# working.net
KiCad netlist of a schematic drawn in EAGLE
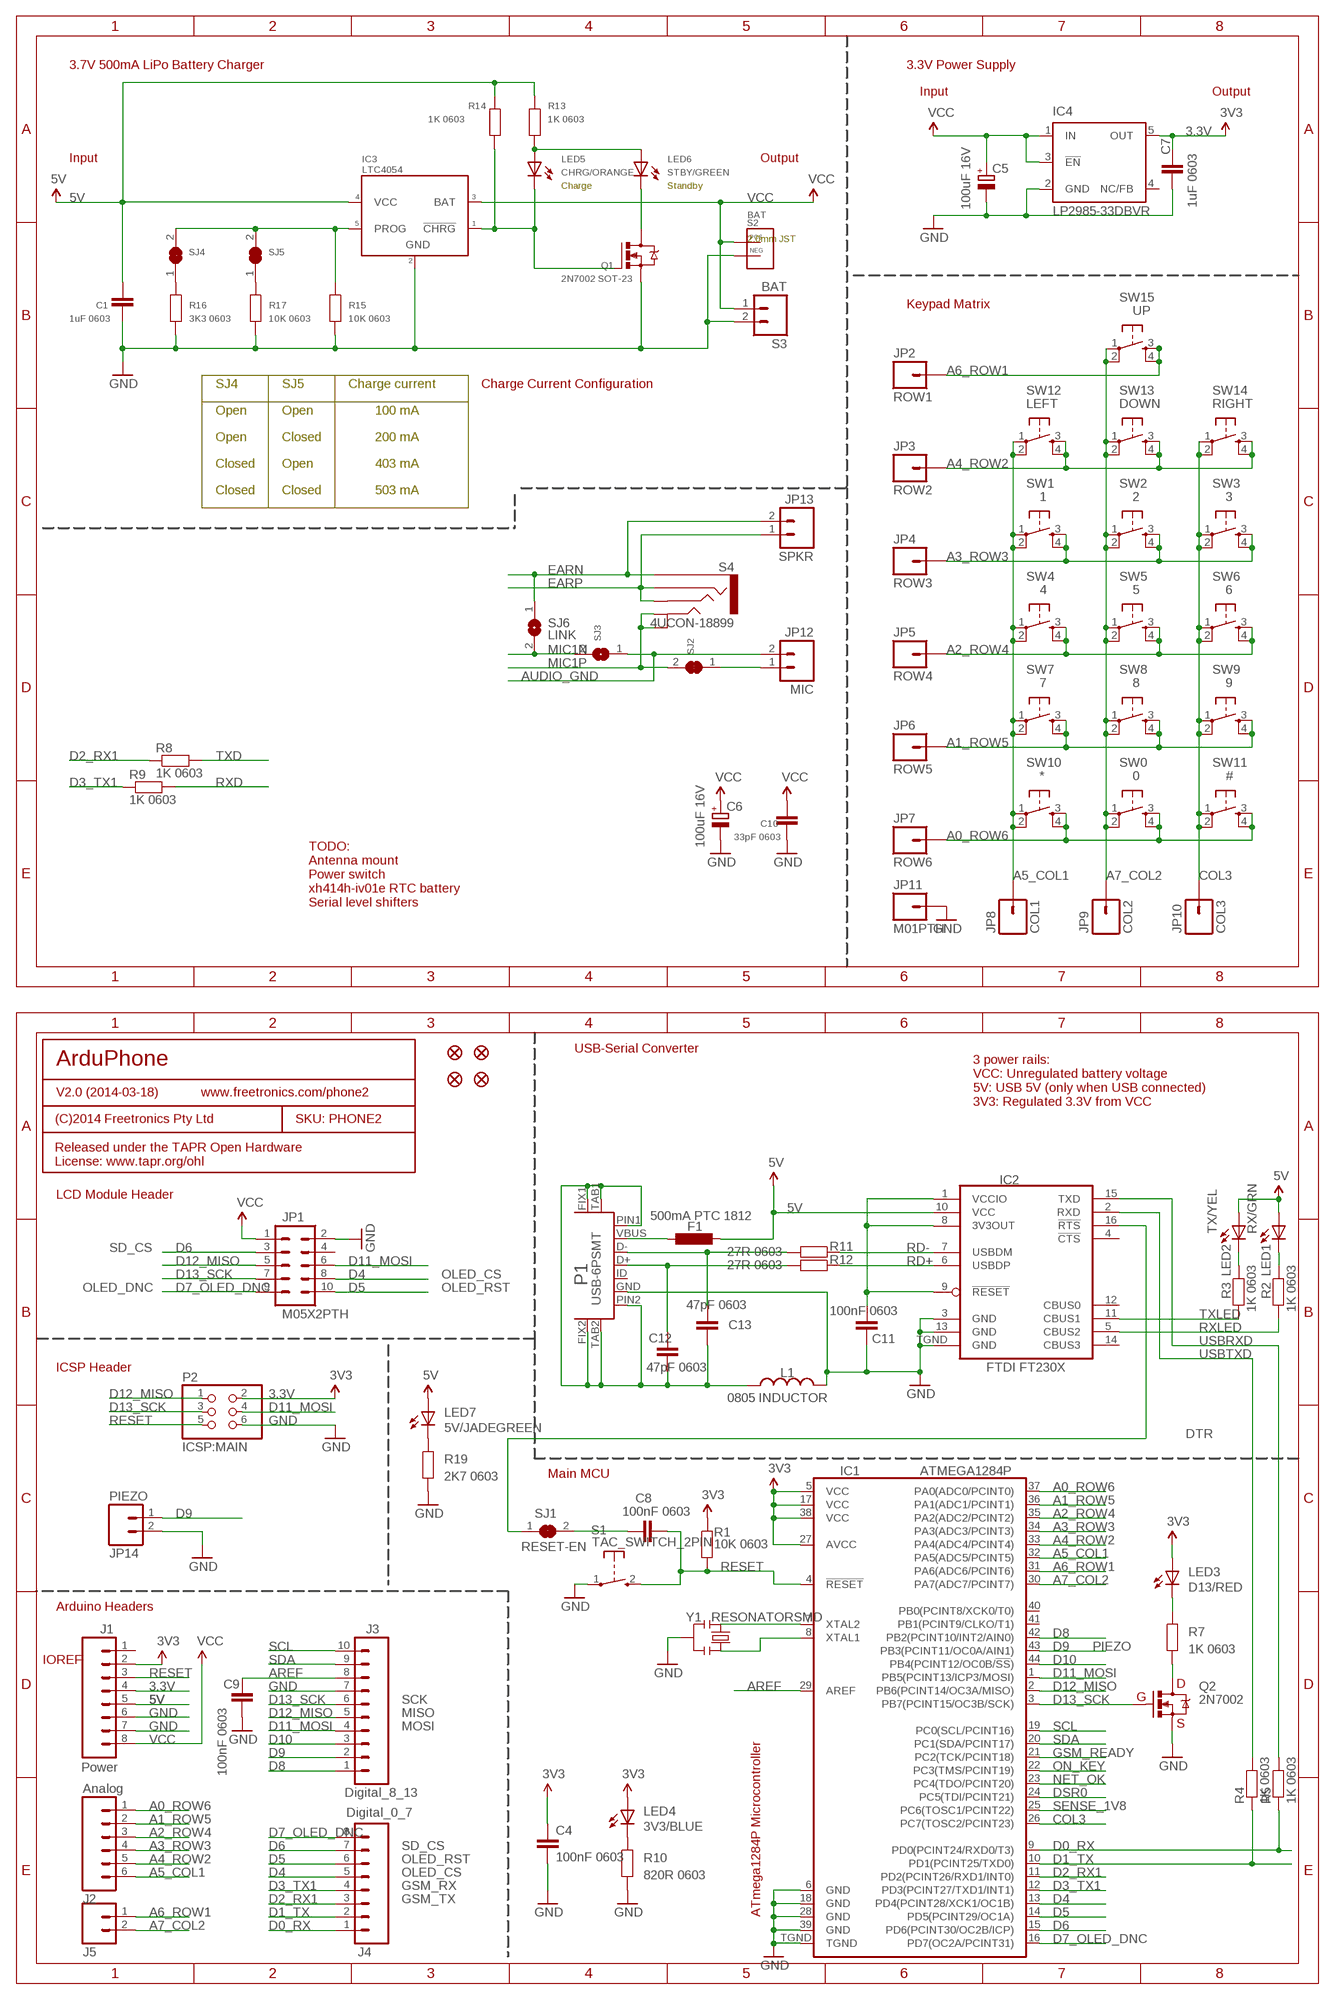
[diagram p0: schematic, sheet 1, part 1 of 2]
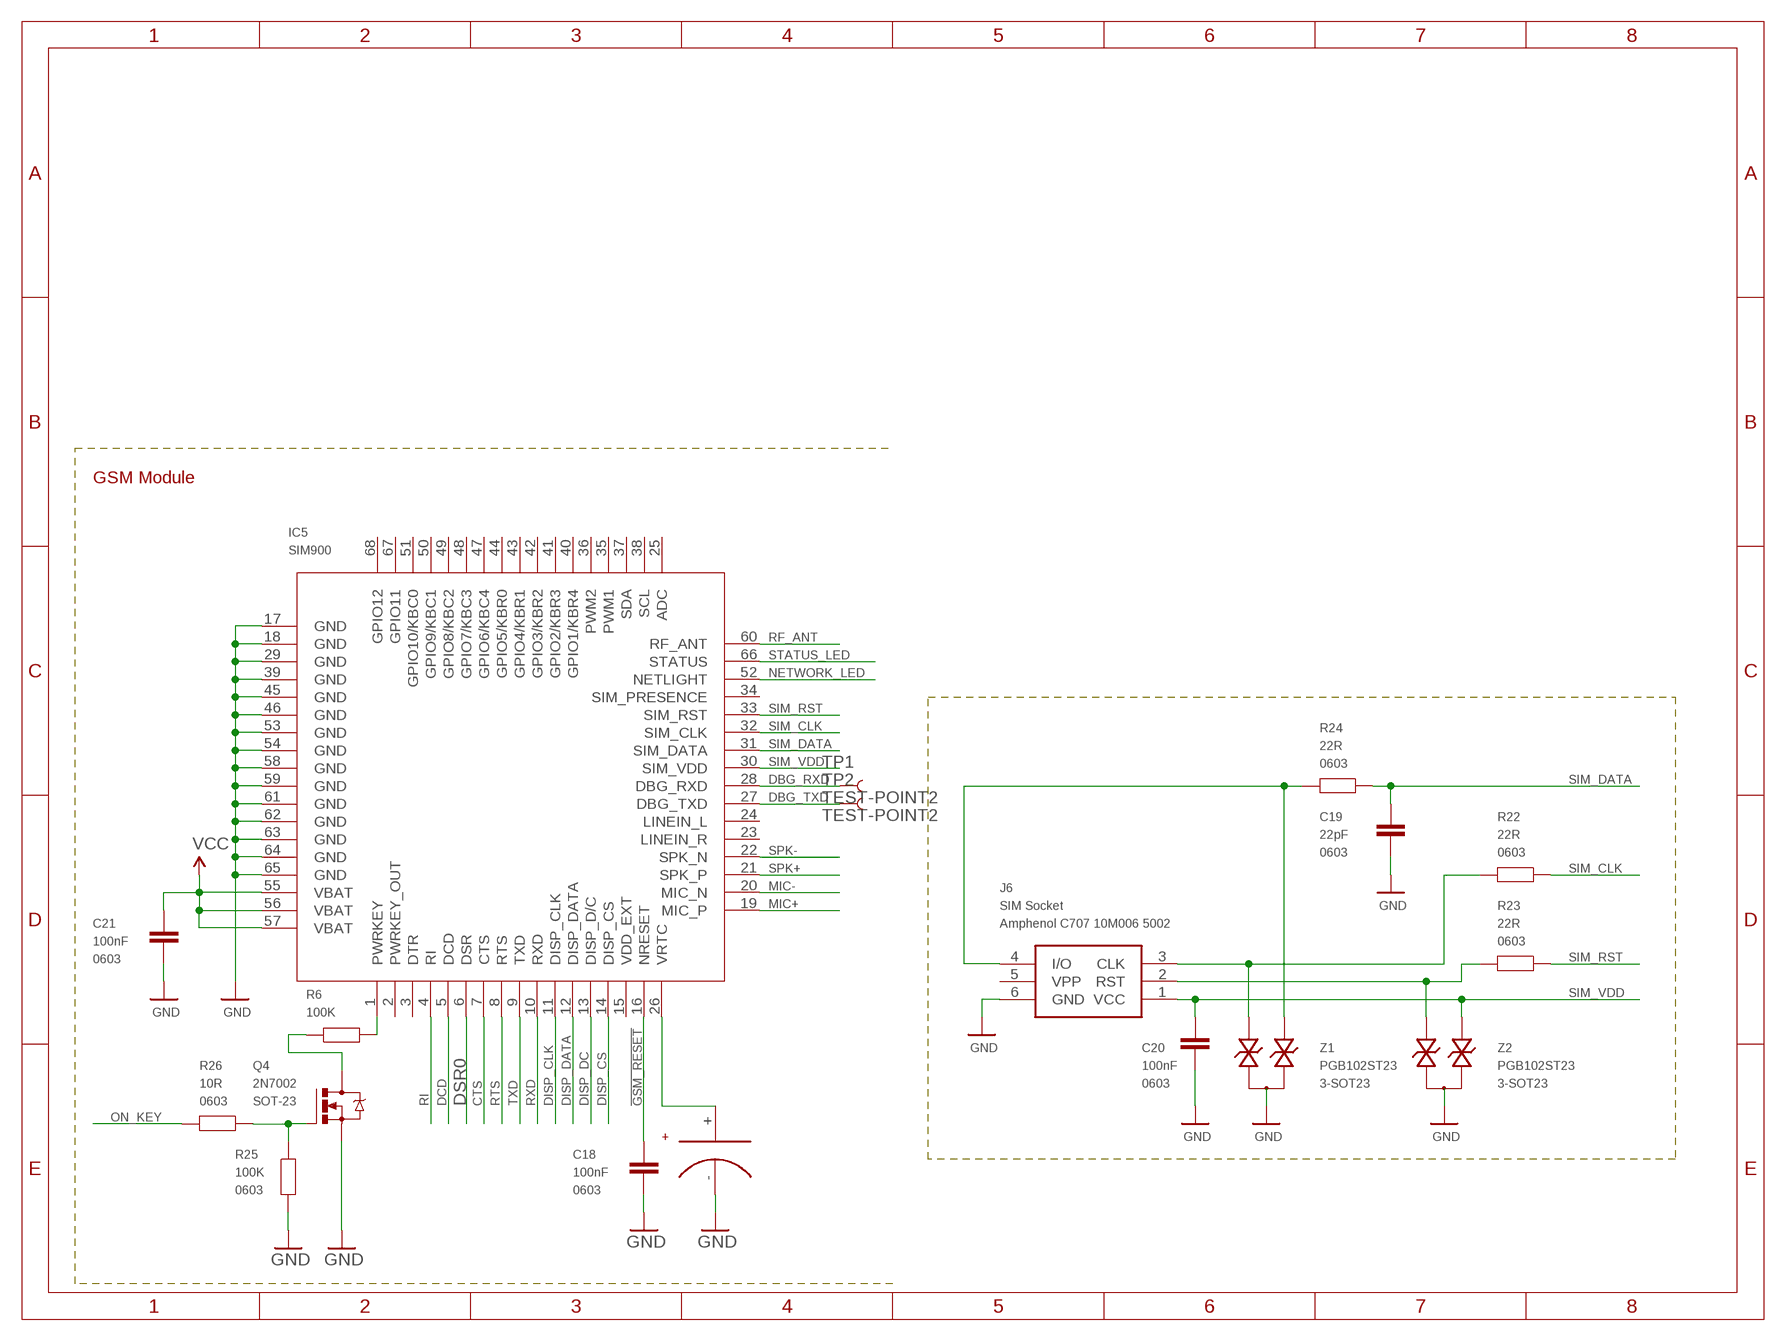
[diagram p1: schematic, sheet 1, part 2 of 2]

(export (version "E")
  (design (tool "Eeschema 10.0.6"))
  (components
    (comp (ref "C1")
      (value "1uF 0603")
      (footprint "eagle-import:0603")
      (libsource (lib "eagle-import") (part "freetronics-master-v1.1_CAP0603"))
    )
    (comp (ref "C4")
      (value "100nF 0603")
      (footprint "eagle-import:0603")
      (libsource (lib "eagle-import") (part "freetronics-master-v1.1_CAP0603"))
    )
    (comp (ref "C5")
      (value "100uF 16V")
      (footprint "eagle-import:PANASONIC_D")
      (libsource (lib "eagle-import") (part "CPOL-EUD"))
    )
    (comp (ref "C6")
      (value "100uF 16V")
      (footprint "eagle-import:PANASONIC_D")
      (libsource (lib "eagle-import") (part "CPOL-EUD"))
    )
    (comp (ref "C7")
      (value "1uF 0603")
      (footprint "eagle-import:0603")
      (libsource (lib "eagle-import") (part "freetronics-master-v1.1_CAP0603"))
    )
    (comp (ref "C8")
      (value "100nF 0603")
      (footprint "eagle-import:0603")
      (libsource (lib "eagle-import") (part "freetronics-master-v1.1_CAP0603"))
    )
    (comp (ref "C9")
      (value "100nF 0603")
      (footprint "eagle-import:0603")
      (libsource (lib "eagle-import") (part "freetronics-master-v1.1_CAP0603"))
    )
    (comp (ref "C10")
      (value "33pF 0603")
      (footprint "eagle-import:0603@1")
      (libsource (lib "eagle-import") (part "CAP0603"))
    )
    (comp (ref "C11")
      (value "100nF 0603")
      (footprint "eagle-import:0603")
      (libsource (lib "eagle-import") (part "freetronics-master-v1.1_CAP0603"))
    )
    (comp (ref "C12")
      (value "47pF 0603")
      (footprint "eagle-import:C0603")
      (libsource (lib "eagle-import") (part "C-EUC0603"))
    )
    (comp (ref "C13")
      (value "47pF 0603")
      (footprint "eagle-import:C0603")
      (libsource (lib "eagle-import") (part "C-EUC0603"))
    )
    (comp (ref "C18")
      (value "100nF")
      (footprint "eagle-import:0603")
      (fields (field (name "PACKAGE") "0603"))
      (libsource (lib "eagle-import") (part "freetronics-master-v1_CAP0603"))
    )
    (comp (ref "C19")
      (value "22pF")
      (footprint "eagle-import:0603")
      (fields (field (name "PACKAGE") "0603"))
      (libsource (lib "eagle-import") (part "freetronics-master-v1_CAP0603"))
    )
    (comp (ref "C20")
      (value "100nF")
      (footprint "eagle-import:0603")
      (fields (field (name "PACKAGE") "0603"))
      (libsource (lib "eagle-import") (part "freetronics-master-v1_CAP0603"))
    )
    (comp (ref "C21")
      (value "100nF")
      (footprint "eagle-import:0603")
      (fields (field (name "PACKAGE") "0603"))
      (libsource (lib "eagle-import") (part "freetronics-master-v1_CAP0603"))
    )
    (comp (ref "F1")
      (value "500mA PTC 1812")
      (footprint "eagle-import:L1812")
      (libsource (lib "eagle-import") (part "L-EUL1812"))
    )
    (comp (ref "IC1")
      (value "ATMEGA1284P")
      (footprint "eagle-import:QFN-44M1")
      (libsource (lib "eagle-import") (part "ATMEGA1284P"))
    )
    (comp (ref "IC2")
      (value "FT230X")
      (footprint "eagle-import:QFN-16")
      (libsource (lib "eagle-import") (part "FT230X"))
    )
    (comp (ref "IC3")
      (value "LTC4054")
      (footprint "eagle-import:SOT23-5")
      (libsource (lib "eagle-import") (part "LTC4054"))
    )
    (comp (ref "IC4")
      (value "LP2985-33DBVR")
      (footprint "eagle-import:TEXAS_SOT23-DBV")
      (libsource (lib "eagle-import") (part "TEXAS_TPS77033"))
    )
    (comp (ref "IC5")
      (value "SIM900")
      (footprint "eagle-import:SIM900")
      (libsource (lib "eagle-import") (part "SIM900"))
    )
    (comp (ref "J1")
      (value "Power")
      (footprint "eagle-import:1X08")
      (libsource (lib "eagle-import") (part "M08"))
    )
    (comp (ref "J2")
      (value "Analog")
      (footprint "eagle-import:1X06")
      (libsource (lib "eagle-import") (part "M06SIP"))
    )
    (comp (ref "J3")
      (value "Digital_8_13")
      (footprint "eagle-import:1X10")
      (libsource (lib "eagle-import") (part "M100.1"))
    )
    (comp (ref "J4")
      (value "Digital_0_7")
      (footprint "eagle-import:1X08")
      (libsource (lib "eagle-import") (part "M08"))
    )
    (comp (ref "J5")
      (value "M02PTH")
      (footprint "eagle-import:1X02")
      (libsource (lib "eagle-import") (part "M02PTH"))
    )
    (comp (ref "J6")
      (value "SIM Socket")
      (footprint "eagle-import:SIMHOLDER3")
      (fields (field (name "ID") "Amphenol C707 10M006 5002"))
      (libsource (lib "eagle-import") (part "SIMHOLDER3"))
    )
    (comp (ref "JP1")
      (value "M05X2PTH")
      (footprint "eagle-import:AVR_ICSP")
      (libsource (lib "eagle-import") (part "M05X2PTH"))
    )
    (comp (ref "JP2")
      (value "ROW1")
      (footprint "eagle-import:1X01")
      (libsource (lib "eagle-import") (part "M01PTH"))
    )
    (comp (ref "JP3")
      (value "ROW2")
      (footprint "eagle-import:1X01")
      (libsource (lib "eagle-import") (part "M01PTH"))
    )
    (comp (ref "JP4")
      (value "ROW3")
      (footprint "eagle-import:1X01")
      (libsource (lib "eagle-import") (part "M01PTH"))
    )
    (comp (ref "JP5")
      (value "ROW4")
      (footprint "eagle-import:1X01")
      (libsource (lib "eagle-import") (part "M01PTH"))
    )
    (comp (ref "JP6")
      (value "ROW5")
      (footprint "eagle-import:1X01")
      (libsource (lib "eagle-import") (part "M01PTH"))
    )
    (comp (ref "JP7")
      (value "ROW6")
      (footprint "eagle-import:1X01")
      (libsource (lib "eagle-import") (part "M01PTH"))
    )
    (comp (ref "JP8")
      (value "COL1")
      (footprint "eagle-import:1X01")
      (libsource (lib "eagle-import") (part "M01PTH"))
    )
    (comp (ref "JP9")
      (value "COL2")
      (footprint "eagle-import:1X01")
      (libsource (lib "eagle-import") (part "M01PTH"))
    )
    (comp (ref "JP10")
      (value "COL3")
      (footprint "eagle-import:1X01")
      (libsource (lib "eagle-import") (part "M01PTH"))
    )
    (comp (ref "JP11")
      (value "M01PTH")
      (footprint "eagle-import:1X01")
      (libsource (lib "eagle-import") (part "freetronics-original_M01PTH"))
    )
    (comp (ref "JP12")
      (value "MIC")
      (footprint "eagle-import:1X02")
      (libsource (lib "eagle-import") (part "M02PTH"))
    )
    (comp (ref "JP13")
      (value "SPKR")
      (footprint "eagle-import:1X02")
      (libsource (lib "eagle-import") (part "M02PTH"))
    )
    (comp (ref "JP14")
      (value "PIEZO")
      (footprint "eagle-import:1X02")
      (libsource (lib "eagle-import") (part "M02PTH"))
    )
    (comp (ref "L1")
      (value "0805 INDUCTOR")
      (footprint "eagle-import:0805-LARGE")
      (libsource (lib "eagle-import") (part "INDUCTOR0805-LARGE"))
    )
    (comp (ref "LED1")
      (value "RX/GRN")
      (footprint "eagle-import:LED-0603")
      (libsource (lib "eagle-import") (part "LED0603"))
    )
    (comp (ref "LED2")
      (value "TX/YEL")
      (footprint "eagle-import:LED-0603")
      (libsource (lib "eagle-import") (part "LED0603"))
    )
    (comp (ref "LED3")
      (value "D13/RED")
      (footprint "eagle-import:LED-0603")
      (libsource (lib "eagle-import") (part "LED0603"))
    )
    (comp (ref "LED4")
      (value "3V3/BLUE")
      (footprint "eagle-import:LED-0603")
      (libsource (lib "eagle-import") (part "LED0603"))
    )
    (comp (ref "LED5")
      (value "CHRG/ORANGE")
      (footprint "eagle-import:LED-0603")
      (libsource (lib "eagle-import") (part "LED0603"))
    )
    (comp (ref "LED6")
      (value "STBY/GREEN")
      (footprint "eagle-import:LED-0603")
      (libsource (lib "eagle-import") (part "LED0603"))
    )
    (comp (ref "LED7")
      (value "5V/JADEGREEN")
      (footprint "eagle-import:LED-0603")
      (libsource (lib "eagle-import") (part "LED0603"))
    )
    (comp (ref "P1")
      (value "USB-6PSMT")
      (footprint "eagle-import:USB-MICROB-MB05PMXX")
      (libsource (lib "eagle-import") (part "USB-6PSMT"))
    )
    (comp (ref "P2")
      (value "ICSP:MAIN")
      (footprint "eagle-import:2X03")
      (libsource (lib "eagle-import") (part "PINHD-2X3"))
    )
    (comp (ref "Q1")
      (value "2N7002 SOT-23")
      (footprint "eagle-import:SOT23-3")
      (libsource (lib "eagle-import") (part "2N7002"))
    )
    (comp (ref "Q2")
      (value "2N7002")
      (footprint "eagle-import:SOT23-3")
      (libsource (lib "eagle-import") (part "MOSFET-NCHANNELSMD"))
    )
    (comp (ref "Q4")
      (value "2N7002")
      (footprint "eagle-import:SOT23-3")
      (fields (field (name "PACKAGE") "SOT-23"))
      (libsource (lib "eagle-import") (part "2N7002"))
    )
    (comp (ref "R1")
      (value "10K 0603")
      (footprint "eagle-import:0603")
      (libsource (lib "eagle-import") (part "freetronics-master-v1.1_RESISTOR0603"))
    )
    (comp (ref "R2")
      (value "1K 0603")
      (footprint "eagle-import:0603")
      (libsource (lib "eagle-import") (part "freetronics-master-v1.1_RESISTOR0603"))
    )
    (comp (ref "R3")
      (value "1K 0603")
      (footprint "eagle-import:0603")
      (libsource (lib "eagle-import") (part "freetronics-master-v1.1_RESISTOR0603"))
    )
    (comp (ref "R4")
      (value "1K 0603")
      (footprint "eagle-import:0603")
      (libsource (lib "eagle-import") (part "freetronics-master-v1.1_RESISTOR0603"))
    )
    (comp (ref "R5")
      (value "1K 0603")
      (footprint "eagle-import:0603")
      (libsource (lib "eagle-import") (part "freetronics-master-v1.1_RESISTOR0603"))
    )
    (comp (ref "R6")
      (value "100K")
      (footprint "eagle-import:0603")
      (fields (field (name "PACKAGE") "0603"))
      (libsource (lib "eagle-import") (part "RESISTOR0603"))
    )
    (comp (ref "R7")
      (value "1K 0603")
      (footprint "eagle-import:0603")
      (libsource (lib "eagle-import") (part "freetronics-master-v1.1_RESISTOR0603"))
    )
    (comp (ref "R8")
      (value "1K 0603")
      (footprint "eagle-import:0603")
      (libsource (lib "eagle-import") (part "freetronics-master-v1.1_RESISTOR0603"))
    )
    (comp (ref "R9")
      (value "1K 0603")
      (footprint "eagle-import:0603")
      (libsource (lib "eagle-import") (part "freetronics-master-v1.1_RESISTOR0603"))
    )
    (comp (ref "R10")
      (value "820R 0603")
      (footprint "eagle-import:0603")
      (libsource (lib "eagle-import") (part "freetronics-master-v1.1_RESISTOR0603"))
    )
    (comp (ref "R11")
      (value "27R 0603")
      (footprint "eagle-import:0603")
      (libsource (lib "eagle-import") (part "freetronics-master-v1.1_RESISTOR0603"))
    )
    (comp (ref "R12")
      (value "27R 0603")
      (footprint "eagle-import:0603")
      (libsource (lib "eagle-import") (part "freetronics-master-v1.1_RESISTOR0603"))
    )
    (comp (ref "R13")
      (value "1K 0603")
      (footprint "eagle-import:0603")
      (libsource (lib "eagle-import") (part "freetronics-master-v1.1_RESISTOR0603"))
    )
    (comp (ref "R14")
      (value "1K 0603")
      (footprint "eagle-import:0603")
      (libsource (lib "eagle-import") (part "freetronics-master-v1.1_RESISTOR0603"))
    )
    (comp (ref "R15")
      (value "10K 0603")
      (footprint "eagle-import:0603")
      (libsource (lib "eagle-import") (part "freetronics-master-v1.1_RESISTOR0603"))
    )
    (comp (ref "R16")
      (value "3K3 0603")
      (footprint "eagle-import:0603")
      (libsource (lib "eagle-import") (part "freetronics-master-v1.1_RESISTOR0603"))
    )
    (comp (ref "R17")
      (value "10K 0603")
      (footprint "eagle-import:0603")
      (libsource (lib "eagle-import") (part "freetronics-master-v1.1_RESISTOR0603"))
    )
    (comp (ref "R19")
      (value "2K7 0603")
      (footprint "eagle-import:0603")
      (libsource (lib "eagle-import") (part "freetronics-master-v1.1_RESISTOR0603"))
    )
    (comp (ref "R22")
      (value "22R")
      (footprint "eagle-import:0603")
      (fields (field (name "PACKAGE") "0603"))
      (libsource (lib "eagle-import") (part "RESISTOR0603"))
    )
    (comp (ref "R23")
      (value "22R")
      (footprint "eagle-import:0603")
      (fields (field (name "PACKAGE") "0603"))
      (libsource (lib "eagle-import") (part "RESISTOR0603"))
    )
    (comp (ref "R24")
      (value "22R")
      (footprint "eagle-import:0603")
      (fields (field (name "PACKAGE") "0603"))
      (libsource (lib "eagle-import") (part "RESISTOR0603"))
    )
    (comp (ref "R25")
      (value "100K")
      (footprint "eagle-import:0603")
      (fields (field (name "PACKAGE") "0603"))
      (libsource (lib "eagle-import") (part "RESISTOR0603"))
    )
    (comp (ref "R26")
      (value "10R")
      (footprint "eagle-import:0603")
      (fields (field (name "PACKAGE") "0603"))
      (libsource (lib "eagle-import") (part "RESISTOR0603"))
    )
    (comp (ref "S1")
      (value "TAC_SWITCH_2PIN")
      (footprint "eagle-import:TACTILE_SWITCH_SMD_2PIN_TINY")
      (libsource (lib "eagle-import") (part "TAC_SWITCH_2PIN"))
    )
    (comp (ref "S2")
      (value "BAT")
      (footprint "eagle-import:JST-2MM-TH-RA")
      (libsource (lib "eagle-import") (part "2P-JST-TH-RAPTH"))
    )
    (comp (ref "S3")
      (value "BAT")
      (footprint "eagle-import:1X02")
      (libsource (lib "eagle-import") (part "M02PTH"))
    )
    (comp (ref "S4")
      (value "4UCON-18899")
      (footprint "eagle-import:4UCON-18899")
      (libsource (lib "eagle-import") (part "AUDIO-JACK-4POLE"))
    )
    (comp (ref "SJ1")
      (value "RESET-EN")
      (footprint "eagle-import:SJC")
      (libsource (lib "eagle-import") (part "SJCN"))
    )
    (comp (ref "SJ2")
      (value "SJCN")
      (footprint "eagle-import:SJC")
      (libsource (lib "eagle-import") (part "SJCN"))
    )
    (comp (ref "SJ3") (value "SJ") (footprint "eagle-import:SJ") (libsource (lib "eagle-import") (part "SJ")))
    (comp (ref "SJ4")
      (value "SJCN")
      (footprint "eagle-import:SJC")
      (libsource (lib "eagle-import") (part "SJCN"))
    )
    (comp (ref "SJ5")
      (value "SJCN")
      (footprint "eagle-import:SJC")
      (libsource (lib "eagle-import") (part "SJCN"))
    )
    (comp (ref "SJ6")
      (value "LINK")
      (footprint "eagle-import:SJ")
      (libsource (lib "eagle-import") (part "SJ"))
    )
    (comp (ref "SW0")
      (value "0")
      (footprint "eagle-import:TACTILE-PTH")
      (libsource (lib "eagle-import") (part "TAC_SWITCHPTH"))
    )
    (comp (ref "SW1")
      (value "1")
      (footprint "eagle-import:TACTILE-PTH")
      (libsource (lib "eagle-import") (part "TAC_SWITCHPTH"))
    )
    (comp (ref "SW2")
      (value "2")
      (footprint "eagle-import:TACTILE-PTH")
      (libsource (lib "eagle-import") (part "TAC_SWITCHPTH"))
    )
    (comp (ref "SW3")
      (value "3")
      (footprint "eagle-import:TACTILE-PTH")
      (libsource (lib "eagle-import") (part "TAC_SWITCHPTH"))
    )
    (comp (ref "SW4")
      (value "4")
      (footprint "eagle-import:TACTILE-PTH")
      (libsource (lib "eagle-import") (part "TAC_SWITCHPTH"))
    )
    (comp (ref "SW5")
      (value "5")
      (footprint "eagle-import:TACTILE-PTH")
      (libsource (lib "eagle-import") (part "TAC_SWITCHPTH"))
    )
    (comp (ref "SW6")
      (value "6")
      (footprint "eagle-import:TACTILE-PTH")
      (libsource (lib "eagle-import") (part "TAC_SWITCHPTH"))
    )
    (comp (ref "SW7")
      (value "7")
      (footprint "eagle-import:TACTILE-PTH")
      (libsource (lib "eagle-import") (part "TAC_SWITCHPTH"))
    )
    (comp (ref "SW8")
      (value "8")
      (footprint "eagle-import:TACTILE-PTH")
      (libsource (lib "eagle-import") (part "TAC_SWITCHPTH"))
    )
    (comp (ref "SW9")
      (value "9")
      (footprint "eagle-import:TACTILE-PTH")
      (libsource (lib "eagle-import") (part "TAC_SWITCHPTH"))
    )
    (comp (ref "SW10")
      (value "*")
      (footprint "eagle-import:TACTILE-PTH")
      (libsource (lib "eagle-import") (part "TAC_SWITCHPTH"))
    )
    (comp (ref "SW11")
      (value "#")
      (footprint "eagle-import:TACTILE-PTH")
      (libsource (lib "eagle-import") (part "TAC_SWITCHPTH"))
    )
    (comp (ref "SW12")
      (value "LEFT")
      (footprint "eagle-import:TACTILE-PTH")
      (libsource (lib "eagle-import") (part "TAC_SWITCHPTH"))
    )
    (comp (ref "SW13")
      (value "DOWN")
      (footprint "eagle-import:TACTILE-PTH")
      (libsource (lib "eagle-import") (part "TAC_SWITCHPTH"))
    )
    (comp (ref "SW14")
      (value "RIGHT")
      (footprint "eagle-import:TACTILE-PTH")
      (libsource (lib "eagle-import") (part "TAC_SWITCHPTH"))
    )
    (comp (ref "SW15")
      (value "UP")
      (footprint "eagle-import:TACTILE-PTH")
      (libsource (lib "eagle-import") (part "TAC_SWITCHPTH"))
    )
    (comp (ref "TP1")
      (value "TEST-POINT2")
      (footprint "eagle-import:PAD.02X.02")
      (libsource (lib "eagle-import") (part "TEST-POINT2"))
    )
    (comp (ref "TP2")
      (value "TEST-POINT2")
      (footprint "eagle-import:PAD.02X.02")
      (libsource (lib "eagle-import") (part "TEST-POINT2"))
    )
    (comp (ref "U$5")
      (value "FIDUCIAL1X2.5")
      (footprint "eagle-import:FIDUCIAL-1X2.5")
      (libsource (lib "eagle-import") (part "FIDUCIAL1X2.5"))
    )
    (comp (ref "U$6")
      (value "FIDUCIAL1X2.5")
      (footprint "eagle-import:FIDUCIAL-1X2.5")
      (libsource (lib "eagle-import") (part "FIDUCIAL1X2.5"))
    )
    (comp (ref "U$7")
      (value "FIDUCIAL1X2.5")
      (footprint "eagle-import:FIDUCIAL-1X2.5")
      (libsource (lib "eagle-import") (part "FIDUCIAL1X2.5"))
    )
    (comp (ref "U$9")
      (value "XH414H-IV01E")
      (footprint "eagle-import:414-VA5R")
      (libsource (lib "eagle-import") (part "SUPERCAPPAS"))
    )
    (comp (ref "U$14")
      (value "FIDUCIAL1X2.5")
      (footprint "eagle-import:FIDUCIAL-1X2.5")
      (libsource (lib "eagle-import") (part "FIDUCIAL1X2.5"))
    )
    (comp (ref "Y1")
      (value "RESONATORSMD")
      (footprint "eagle-import:RESONATOR-SMD")
      (libsource (lib "eagle-import") (part "RESONATORSMD"))
    )
    (comp (ref "Z1")
      (value "PGB102ST23")
      (footprint "eagle-import:SOT23-3")
      (fields (field (name "PACKAGE") "3-SOT23"))
      (libsource (lib "eagle-import") (part "PGB102ST23"))
    )
    (comp (ref "Z2")
      (value "PGB102ST23")
      (footprint "eagle-import:SOT23-3")
      (fields (field (name "PACKAGE") "3-SOT23"))
      (libsource (lib "eagle-import") (part "PGB102ST23"))
    )
  )
  (nets
    (net (code "1") (name "/A0_ROW6") (class "Default")
      (node (ref "IC1") (pin "37") (pinfunction "PA0(ADC0/PCINT0)_37") (pintype "bidirectional"))
      (node (ref "J2") (pin "1") (pinfunction "1_1") (pintype "passive"))
      (node (ref "JP7") (pin "1") (pinfunction "1_1") (pintype "passive"))
      (node (ref "SW0") (pin "3") (pinfunction "3_3") (pintype "passive"))
      (node (ref "SW0") (pin "4") (pinfunction "4_4") (pintype "passive"))
      (node (ref "SW10") (pin "3") (pinfunction "3_3") (pintype "passive"))
      (node (ref "SW10") (pin "4") (pinfunction "4_4") (pintype "passive"))
      (node (ref "SW11") (pin "3") (pinfunction "3_3") (pintype "passive"))
      (node (ref "SW11") (pin "4") (pinfunction "4_4") (pintype "passive"))
    )
    (net (code "2") (name "/A1_ROW5") (class "Default")
      (node (ref "IC1") (pin "36") (pinfunction "PA1(ADC1/PCINT1)_36") (pintype "bidirectional"))
      (node (ref "J2") (pin "2") (pinfunction "2_2") (pintype "passive"))
      (node (ref "JP6") (pin "1") (pinfunction "1_1") (pintype "passive"))
      (node (ref "SW7") (pin "3") (pinfunction "3_3") (pintype "passive"))
      (node (ref "SW7") (pin "4") (pinfunction "4_4") (pintype "passive"))
      (node (ref "SW8") (pin "3") (pinfunction "3_3") (pintype "passive"))
      (node (ref "SW8") (pin "4") (pinfunction "4_4") (pintype "passive"))
      (node (ref "SW9") (pin "3") (pinfunction "3_3") (pintype "passive"))
      (node (ref "SW9") (pin "4") (pinfunction "4_4") (pintype "passive"))
    )
    (net (code "3") (name "/A2_ROW4") (class "Default")
      (node (ref "IC1") (pin "35") (pinfunction "PA2(ADC2/PCINT2)_35") (pintype "bidirectional"))
      (node (ref "J2") (pin "3") (pinfunction "3_3") (pintype "passive"))
      (node (ref "JP5") (pin "1") (pinfunction "1_1") (pintype "passive"))
      (node (ref "SW4") (pin "3") (pinfunction "3_3") (pintype "passive"))
      (node (ref "SW4") (pin "4") (pinfunction "4_4") (pintype "passive"))
      (node (ref "SW5") (pin "3") (pinfunction "3_3") (pintype "passive"))
      (node (ref "SW5") (pin "4") (pinfunction "4_4") (pintype "passive"))
      (node (ref "SW6") (pin "3") (pinfunction "3_3") (pintype "passive"))
      (node (ref "SW6") (pin "4") (pinfunction "4_4") (pintype "passive"))
    )
    (net (code "4") (name "/A3_ROW3") (class "Default")
      (node (ref "IC1") (pin "34") (pinfunction "PA3(ADC3/PCINT3)_34") (pintype "bidirectional"))
      (node (ref "J2") (pin "4") (pinfunction "4_4") (pintype "passive"))
      (node (ref "JP4") (pin "1") (pinfunction "1_1") (pintype "passive"))
      (node (ref "SW1") (pin "3") (pinfunction "3_3") (pintype "passive"))
      (node (ref "SW1") (pin "4") (pinfunction "4_4") (pintype "passive"))
      (node (ref "SW2") (pin "3") (pinfunction "3_3") (pintype "passive"))
      (node (ref "SW2") (pin "4") (pinfunction "4_4") (pintype "passive"))
      (node (ref "SW3") (pin "3") (pinfunction "3_3") (pintype "passive"))
      (node (ref "SW3") (pin "4") (pinfunction "4_4") (pintype "passive"))
    )
    (net (code "5") (name "/A4_ROW2") (class "Default")
      (node (ref "IC1") (pin "33") (pinfunction "PA4(ADC4/PCINT4)_33") (pintype "bidirectional"))
      (node (ref "J2") (pin "5") (pinfunction "5_5") (pintype "passive"))
      (node (ref "JP3") (pin "1") (pinfunction "1_1") (pintype "passive"))
      (node (ref "SW12") (pin "3") (pinfunction "3_3") (pintype "passive"))
      (node (ref "SW12") (pin "4") (pinfunction "4_4") (pintype "passive"))
      (node (ref "SW13") (pin "3") (pinfunction "3_3") (pintype "passive"))
      (node (ref "SW13") (pin "4") (pinfunction "4_4") (pintype "passive"))
      (node (ref "SW14") (pin "3") (pinfunction "3_3") (pintype "passive"))
      (node (ref "SW14") (pin "4") (pinfunction "4_4") (pintype "passive"))
    )
    (net (code "6") (name "/A5_COL1") (class "Default")
      (node (ref "IC1") (pin "32") (pinfunction "PA5(ADC5/PCINT5)_32") (pintype "bidirectional"))
      (node (ref "J2") (pin "6") (pinfunction "6_6") (pintype "passive"))
      (node (ref "JP8") (pin "1") (pinfunction "1_1") (pintype "passive"))
      (node (ref "SW1") (pin "1") (pinfunction "1_1") (pintype "passive"))
      (node (ref "SW1") (pin "2") (pinfunction "2_2") (pintype "passive"))
      (node (ref "SW10") (pin "1") (pinfunction "1_1") (pintype "passive"))
      (node (ref "SW10") (pin "2") (pinfunction "2_2") (pintype "passive"))
      (node (ref "SW12") (pin "1") (pinfunction "1_1") (pintype "passive"))
      (node (ref "SW12") (pin "2") (pinfunction "2_2") (pintype "passive"))
      (node (ref "SW4") (pin "1") (pinfunction "1_1") (pintype "passive"))
      (node (ref "SW4") (pin "2") (pinfunction "2_2") (pintype "passive"))
      (node (ref "SW7") (pin "1") (pinfunction "1_1") (pintype "passive"))
      (node (ref "SW7") (pin "2") (pinfunction "2_2") (pintype "passive"))
    )
    (net (code "7") (name "/A6_ROW1") (class "Default")
      (node (ref "IC1") (pin "31") (pinfunction "PA6(ADC6/PCINT6)_31") (pintype "bidirectional"))
      (node (ref "J5") (pin "1") (pinfunction "1_1") (pintype "passive"))
      (node (ref "JP2") (pin "1") (pinfunction "1_1") (pintype "passive"))
      (node (ref "SW15") (pin "3") (pinfunction "3_3") (pintype "passive"))
      (node (ref "SW15") (pin "4") (pinfunction "4_4") (pintype "passive"))
    )
    (net (code "8") (name "/A7_COL2") (class "Default")
      (node (ref "IC1") (pin "30") (pinfunction "PA7(ADC7/PCINT7)_30") (pintype "bidirectional"))
      (node (ref "J5") (pin "2") (pinfunction "2_2") (pintype "passive"))
      (node (ref "JP9") (pin "1") (pinfunction "1_1") (pintype "passive"))
      (node (ref "SW0") (pin "1") (pinfunction "1_1") (pintype "passive"))
      (node (ref "SW0") (pin "2") (pinfunction "2_2") (pintype "passive"))
      (node (ref "SW13") (pin "1") (pinfunction "1_1") (pintype "passive"))
      (node (ref "SW13") (pin "2") (pinfunction "2_2") (pintype "passive"))
      (node (ref "SW15") (pin "1") (pinfunction "1_1") (pintype "passive"))
      (node (ref "SW15") (pin "2") (pinfunction "2_2") (pintype "passive"))
      (node (ref "SW2") (pin "1") (pinfunction "1_1") (pintype "passive"))
      (node (ref "SW2") (pin "2") (pinfunction "2_2") (pintype "passive"))
      (node (ref "SW5") (pin "1") (pinfunction "1_1") (pintype "passive"))
      (node (ref "SW5") (pin "2") (pinfunction "2_2") (pintype "passive"))
      (node (ref "SW8") (pin "1") (pinfunction "1_1") (pintype "passive"))
      (node (ref "SW8") (pin "2") (pinfunction "2_2") (pintype "passive"))
    )
    (net (code "9") (name "/AREF") (class "Default")
      (node (ref "C9") (pin "1") (pinfunction "1_1") (pintype "passive"))
      (node (ref "IC1") (pin "29") (pinfunction "AREF_29") (pintype "bidirectional"))
      (node (ref "J3") (pin "8") (pinfunction "8_8") (pintype "passive"))
    )
    (net (code "10") (name "/AUDIO_GND") (class "Default")
      (node (ref "JP12") (pin "2") (pinfunction "2_2") (pintype "passive"))
      (node (ref "SJ3") (pin "1") (pinfunction "1_1") (pintype "passive"))
    )
    (net (code "11") (name "/COL3") (class "Default")
      (node (ref "IC1") (pin "26") (pinfunction "PC7(TOSC2/PCINT23)_26") (pintype "bidirectional"))
      (node (ref "JP10") (pin "1") (pinfunction "1_1") (pintype "passive"))
      (node (ref "SW11") (pin "1") (pinfunction "1_1") (pintype "passive"))
      (node (ref "SW11") (pin "2") (pinfunction "2_2") (pintype "passive"))
      (node (ref "SW14") (pin "1") (pinfunction "1_1") (pintype "passive"))
      (node (ref "SW14") (pin "2") (pinfunction "2_2") (pintype "passive"))
      (node (ref "SW3") (pin "1") (pinfunction "1_1") (pintype "passive"))
      (node (ref "SW3") (pin "2") (pinfunction "2_2") (pintype "passive"))
      (node (ref "SW6") (pin "1") (pinfunction "1_1") (pintype "passive"))
      (node (ref "SW6") (pin "2") (pinfunction "2_2") (pintype "passive"))
      (node (ref "SW9") (pin "1") (pinfunction "1_1") (pintype "passive"))
      (node (ref "SW9") (pin "2") (pinfunction "2_2") (pintype "passive"))
    )
    (net (code "12") (name "/CTS") (class "Default")
      (node (ref "IC5") (pin "7") (pinfunction "CTS_7") (pintype "output"))
    )
    (net (code "13") (name "/D0_RX") (class "Default")
      (node (ref "IC1") (pin "9") (pinfunction "PD0(PCINT24/RXD0/T3)_9") (pintype "bidirectional"))
      (node (ref "J4") (pin "1") (pinfunction "1_1") (pintype "passive"))
      (node (ref "R5") (pin "1") (pinfunction "1_1") (pintype "passive"))
    )
    (net (code "14") (name "/D1_TX") (class "Default")
      (node (ref "IC1") (pin "10") (pinfunction "PD1(PCINT25/TXD0)_10") (pintype "bidirectional"))
      (node (ref "J4") (pin "2") (pinfunction "2_2") (pintype "passive"))
      (node (ref "R4") (pin "1") (pinfunction "1_1") (pintype "passive"))
    )
    (net (code "15") (name "/D2_RX1") (class "Default")
      (node (ref "IC1") (pin "11") (pinfunction "PD2(PCINT26/RXD1/INT0)_11") (pintype "bidirectional"))
      (node (ref "J4") (pin "3") (pinfunction "3_3") (pintype "passive"))
      (node (ref "R8") (pin "1") (pinfunction "1_1") (pintype "passive"))
    )
    (net (code "16") (name "/D3_TX1") (class "Default")
      (node (ref "IC1") (pin "12") (pinfunction "PD3(PCINT27/TXD1/INT1)_12") (pintype "bidirectional"))
      (node (ref "J4") (pin "4") (pinfunction "4_4") (pintype "passive"))
      (node (ref "R9") (pin "1") (pinfunction "1_1") (pintype "passive"))
    )
    (net (code "17") (name "/D4") (class "Default")
      (node (ref "IC1") (pin "13") (pinfunction "PD4(PCINT28/XCK1/OC1B)_13") (pintype "bidirectional"))
      (node (ref "J4") (pin "5") (pinfunction "5_5") (pintype "passive"))
      (node (ref "JP1") (pin "8") (pinfunction "8_8") (pintype "passive"))
    )
    (net (code "18") (name "/D5") (class "Default")
      (node (ref "IC1") (pin "14") (pinfunction "PD5(PCINT29/OC1A)_14") (pintype "bidirectional"))
      (node (ref "J4") (pin "6") (pinfunction "6_6") (pintype "passive"))
      (node (ref "JP1") (pin "10") (pinfunction "10_10") (pintype "passive"))
    )
    (net (code "19") (name "/D6") (class "Default")
      (node (ref "IC1") (pin "15") (pinfunction "PD6(PCINT30/OC2B/ICP)_15") (pintype "bidirectional"))
      (node (ref "J4") (pin "7") (pinfunction "7_7") (pintype "passive"))
      (node (ref "JP1") (pin "3") (pinfunction "3_3") (pintype "passive"))
    )
    (net (code "20") (name "/D7_OLED_DNC") (class "Default")
      (node (ref "IC1") (pin "16") (pinfunction "PD7(OC2A/PCINT31)_16") (pintype "bidirectional"))
      (node (ref "J4") (pin "8") (pinfunction "8_8") (pintype "passive"))
      (node (ref "JP1") (pin "9") (pinfunction "9_9") (pintype "passive"))
    )
    (net (code "21") (name "/D8") (class "Default")
      (node (ref "IC1") (pin "42") (pinfunction "PB2(PCINT10/INT2/AIN0)_42") (pintype "bidirectional"))
      (node (ref "J3") (pin "1") (pinfunction "1_1") (pintype "passive"))
    )
    (net (code "22") (name "/D9") (class "Default")
      (node (ref "IC1") (pin "43") (pinfunction "PB3(PCINT11/OC0A/AIN1)_43") (pintype "bidirectional"))
      (node (ref "J3") (pin "2") (pinfunction "2_2") (pintype "passive"))
      (node (ref "JP14") (pin "1") (pinfunction "1_1") (pintype "passive"))
    )
    (net (code "23") (name "/D10") (class "Default")
      (node (ref "IC1") (pin "44") (pinfunction "PB4(PCINT12/OC0B/~{SS})_44") (pintype "bidirectional"))
      (node (ref "J3") (pin "3") (pinfunction "3_3") (pintype "passive"))
    )
    (net (code "24") (name "/D11_MOSI") (class "Default")
      (node (ref "IC1") (pin "1") (pinfunction "PB5(PCINT13/ICP3/MOSI)_1") (pintype "bidirectional"))
      (node (ref "J3") (pin "4") (pinfunction "4_4") (pintype "passive"))
      (node (ref "JP1") (pin "6") (pinfunction "6_6") (pintype "passive"))
      (node (ref "P2") (pin "4") (pinfunction "4_4") (pintype "passive"))
    )
    (net (code "25") (name "/D12_MISO") (class "Default")
      (node (ref "IC1") (pin "2") (pinfunction "PB6(PCINT14/OC3A/MISO)_2") (pintype "bidirectional"))
      (node (ref "J3") (pin "5") (pinfunction "5_5") (pintype "passive"))
      (node (ref "JP1") (pin "5") (pinfunction "5_5") (pintype "passive"))
      (node (ref "P2") (pin "1") (pinfunction "1_1") (pintype "passive"))
    )
    (net (code "26") (name "/D13_SCK") (class "Default")
      (node (ref "IC1") (pin "3") (pinfunction "PB7(PCINT15/OC3B/SCK)_3") (pintype "bidirectional"))
      (node (ref "J3") (pin "6") (pinfunction "6_6") (pintype "passive"))
      (node (ref "JP1") (pin "7") (pinfunction "7_7") (pintype "passive"))
      (node (ref "P2") (pin "3") (pinfunction "3_3") (pintype "passive"))
      (node (ref "Q2") (pin "1") (pinfunction "G_1") (pintype "passive"))
    )
    (net (code "27") (name "/DBG_RXD") (class "Default")
      (node (ref "IC5") (pin "28") (pinfunction "DBG_RXD_28") (pintype "input"))
      (node (ref "TP1") (pin "P$1") (pinfunction "1_P$1") (pintype "bidirectional"))
    )
    (net (code "28") (name "/DBG_TXD") (class "Default")
      (node (ref "IC5") (pin "27") (pinfunction "DBG_TXD_27") (pintype "output"))
      (node (ref "TP2") (pin "P$1") (pinfunction "1_P$1") (pintype "bidirectional"))
    )
    (net (code "29") (name "/DCD") (class "Default")
      (node (ref "IC5") (pin "5") (pinfunction "DCD_5") (pintype "output"))
    )
    (net (code "30") (name "/DISP_CLK") (class "Default")
      (node (ref "IC5") (pin "11") (pinfunction "DISP_CLK_11") (pintype "output"))
    )
    (net (code "31") (name "/DISP_CS") (class "Default")
      (node (ref "IC5") (pin "14") (pinfunction "DISP_CS_14") (pintype "output"))
    )
    (net (code "32") (name "/DISP_DATA") (class "Default")
      (node (ref "IC5") (pin "12") (pinfunction "DISP_DATA_12") (pintype "bidirectional"))
    )
    (net (code "33") (name "/DISP_DC") (class "Default")
      (node (ref "IC5") (pin "13") (pinfunction "DISP_D/C_13") (pintype "output"))
    )
    (net (code "34") (name "/DSR0") (class "Default")
      (node (ref "IC1") (pin "24") (pinfunction "PC5(TDI/PCINT21)_24") (pintype "bidirectional"))
      (node (ref "IC5") (pin "6") (pinfunction "DSR_6") (pintype "output"))
    )
    (net (code "35") (name "/DTR") (class "Default")
      (node (ref "IC2") (pin "16") (pinfunction "~{RTS}_16") (pintype "bidirectional"))
      (node (ref "SJ1") (pin "1") (pinfunction "1_1") (pintype "passive"))
    )
    (net (code "36") (name "/EARN") (class "Default")
      (node (ref "JP13") (pin "2") (pinfunction "2_2") (pintype "passive"))
      (node (ref "S4") (pin "1") (pinfunction "1_1") (pintype "bidirectional"))
      (node (ref "SJ6") (pin "1") (pinfunction "1_1") (pintype "passive"))
    )
    (net (code "37") (name "/EARP") (class "Default")
      (node (ref "JP13") (pin "1") (pinfunction "1_1") (pintype "passive"))
      (node (ref "S4") (pin "3") (pinfunction "3_3") (pintype "bidirectional"))
      (node (ref "S4") (pin "4") (pinfunction "4_4") (pintype "bidirectional"))
    )
    (net (code "38") (name "/GSM_READY") (class "Default")
      (node (ref "IC1") (pin "21") (pinfunction "PC2(TCK/PCINT18)_21") (pintype "bidirectional"))
    )
    (net (code "39") (name "/MIC+") (class "Default")
      (node (ref "IC5") (pin "19") (pinfunction "MIC_P_19") (pintype "input"))
    )
    (net (code "40") (name "/MIC-") (class "Default")
      (node (ref "IC5") (pin "20") (pinfunction "MIC_N_20") (pintype "input"))
    )
    (net (code "41") (name "/MIC1N") (class "Default")
      (node (ref "SJ3") (pin "2") (pinfunction "2_2") (pintype "passive"))
      (node (ref "SJ6") (pin "2") (pinfunction "2_2") (pintype "passive"))
    )
    (net (code "42") (name "/MIC1P") (class "Default")
      (node (ref "S4") (pin "2A") (pinfunction "2A_2A") (pintype "bidirectional"))
      (node (ref "S4") (pin "2B") (pinfunction "2B_2B") (pintype "bidirectional"))
      (node (ref "SJ2") (pin "2") (pinfunction "2_2") (pintype "passive"))
    )
    (net (code "43") (name "/NETWORK_LED") (class "Default")
      (node (ref "IC5") (pin "52") (pinfunction "NETLIGHT_52") (pintype "output"))
    )
    (net (code "44") (name "/NET_OK") (class "Default")
      (node (ref "IC1") (pin "23") (pinfunction "PC4(TDO/PCINT20)_23") (pintype "bidirectional"))
    )
    (net (code "45") (name "/ON_KEY") (class "Default")
      (node (ref "IC1") (pin "22") (pinfunction "PC3(TMS/PCINT19)_22") (pintype "bidirectional"))
      (node (ref "R26") (pin "2") (pinfunction "2_2") (pintype "passive"))
    )
    (net (code "46") (name "/RD+") (class "Default")
      (node (ref "IC2") (pin "6") (pinfunction "USBDP_6") (pintype "bidirectional"))
      (node (ref "R12") (pin "1") (pinfunction "1_1") (pintype "passive"))
    )
    (net (code "47") (name "/RD-") (class "Default")
      (node (ref "IC2") (pin "7") (pinfunction "USBDM_7") (pintype "bidirectional"))
      (node (ref "R11") (pin "1") (pinfunction "1_1") (pintype "passive"))
    )
    (net (code "48") (name "/RESET") (class "Default")
      (node (ref "C8") (pin "2") (pinfunction "2_2") (pintype "passive"))
      (node (ref "IC1") (pin "4") (pinfunction "~{RESET}_4") (pintype "bidirectional"))
      (node (ref "J1") (pin "3") (pinfunction "3_3") (pintype "passive"))
      (node (ref "P2") (pin "5") (pinfunction "5_5") (pintype "passive"))
      (node (ref "R1") (pin "1") (pinfunction "1_1") (pintype "passive"))
      (node (ref "S1") (pin "2") (pinfunction "S_2") (pintype "passive"))
    )
    (net (code "49") (name "/RF_ANT") (class "Default")
      (node (ref "IC5") (pin "60") (pinfunction "RF_ANT_60") (pintype "bidirectional"))
    )
    (net (code "50") (name "/RI") (class "Default")
      (node (ref "IC5") (pin "4") (pinfunction "RI_4") (pintype "output"))
    )
    (net (code "51") (name "/RTS") (class "Default")
      (node (ref "IC5") (pin "8") (pinfunction "RTS_8") (pintype "input"))
    )
    (net (code "52") (name "/RXD") (class "Default")
      (node (ref "IC5") (pin "10") (pinfunction "RXD_10") (pintype "input"))
      (node (ref "R9") (pin "2") (pinfunction "2_2") (pintype "passive"))
    )
    (net (code "53") (name "/RXLED") (class "Default")
      (node (ref "IC2") (pin "5") (pinfunction "CBUS2_5") (pintype "bidirectional"))
      (node (ref "R2") (pin "1") (pinfunction "1_1") (pintype "passive"))
    )
    (net (code "54") (name "/SCL") (class "Default")
      (node (ref "IC1") (pin "19") (pinfunction "PC0(SCL/PCINT16)_19") (pintype "bidirectional"))
      (node (ref "J3") (pin "10") (pinfunction "10_10") (pintype "passive"))
    )
    (net (code "55") (name "/SDA") (class "Default")
      (node (ref "IC1") (pin "20") (pinfunction "PC1(SDA/PCINT17)_20") (pintype "bidirectional"))
      (node (ref "J3") (pin "9") (pinfunction "9_9") (pintype "passive"))
    )
    (net (code "56") (name "/SENSE_1V8") (class "Default")
      (node (ref "IC1") (pin "25") (pinfunction "PC6(TOSC1/PCINT22)_25") (pintype "bidirectional"))
    )
    (net (code "57") (name "/SIM_CLK") (class "Default")
      (node (ref "IC5") (pin "32") (pinfunction "SIM_CLK_32") (pintype "output"))
      (node (ref "R22") (pin "1") (pinfunction "1_1") (pintype "passive"))
    )
    (net (code "58") (name "/SIM_DATA") (class "Default")
      (node (ref "C19") (pin "2") (pinfunction "2_2") (pintype "passive"))
      (node (ref "IC5") (pin "31") (pinfunction "SIM_DATA_31") (pintype "bidirectional"))
      (node (ref "R24") (pin "1") (pinfunction "1_1") (pintype "passive"))
    )
    (net (code "59") (name "/SIM_RST") (class "Default")
      (node (ref "IC5") (pin "33") (pinfunction "SIM_RST_33") (pintype "output"))
      (node (ref "R23") (pin "1") (pinfunction "1_1") (pintype "passive"))
    )
    (net (code "60") (name "/SIM_VDD") (class "Default")
      (node (ref "C20") (pin "2") (pinfunction "2_2") (pintype "passive"))
      (node (ref "IC5") (pin "30") (pinfunction "SIM_VDD_30") (pintype "output"))
      (node (ref "J6") (pin "1") (pinfunction "VCC_1") (pintype "bidirectional"))
      (node (ref "Z2") (pin "2") (pinfunction "P$2_2") (pintype "bidirectional"))
    )
    (net (code "61") (name "/SPK+") (class "Default")
      (node (ref "IC5") (pin "21") (pinfunction "SPK_P_21") (pintype "output"))
    )
    (net (code "62") (name "/SPK-") (class "Default")
      (node (ref "IC5") (pin "22") (pinfunction "SPK_N_22") (pintype "output"))
    )
    (net (code "63") (name "/STATUS_LED") (class "Default")
      (node (ref "IC5") (pin "66") (pinfunction "STATUS_66") (pintype "output"))
    )
    (net (code "64") (name "/TXD") (class "Default")
      (node (ref "IC5") (pin "9") (pinfunction "TXD_9") (pintype "output"))
      (node (ref "R8") (pin "2") (pinfunction "2_2") (pintype "passive"))
    )
    (net (code "65") (name "/TXLED") (class "Default")
      (node (ref "IC2") (pin "11") (pinfunction "CBUS1_11") (pintype "bidirectional"))
      (node (ref "R3") (pin "1") (pinfunction "1_1") (pintype "passive"))
    )
    (net (code "66") (name "/USBRXD") (class "Default")
      (node (ref "IC2") (pin "15") (pinfunction "TXD_15") (pintype "bidirectional"))
      (node (ref "R5") (pin "2") (pinfunction "2_2") (pintype "passive"))
    )
    (net (code "67") (name "/USBTXD") (class "Default")
      (node (ref "IC2") (pin "2") (pinfunction "RXD_2") (pintype "bidirectional"))
      (node (ref "R4") (pin "2") (pinfunction "2_2") (pintype "passive"))
    )
    (net (code "68") (name "/~{GSM_RESET}") (class "Default")
      (node (ref "C18") (pin "2") (pinfunction "2_2") (pintype "passive"))
      (node (ref "IC5") (pin "16") (pinfunction "NRESET_16") (pintype "input"))
    )
    (net (code "69") (name "3V3") (class "Default")
      (node (ref "C4") (pin "1") (pinfunction "1_1") (pintype "passive"))
      (node (ref "C7") (pin "2") (pinfunction "2_2") (pintype "passive"))
      (node (ref "IC1") (pin "17") (pinfunction "VCC_17") (pintype "bidirectional"))
      (node (ref "IC1") (pin "27") (pinfunction "AVCC_27") (pintype "bidirectional"))
      (node (ref "IC1") (pin "38") (pinfunction "VCC_38") (pintype "bidirectional"))
      (node (ref "IC1") (pin "5") (pinfunction "VCC_5") (pintype "bidirectional"))
      (node (ref "IC4") (pin "5") (pinfunction "OUT_5") (pintype "passive"))
      (node (ref "J1") (pin "2") (pinfunction "2_2") (pintype "passive"))
      (node (ref "J1") (pin "4") (pinfunction "4_4") (pintype "passive"))
      (node (ref "LED3") (pin "A") (pinfunction "A_A") (pintype "passive"))
      (node (ref "LED4") (pin "A") (pinfunction "A_A") (pintype "passive"))
      (node (ref "P2") (pin "2") (pinfunction "2_2") (pintype "passive"))
      (node (ref "R1") (pin "2") (pinfunction "2_2") (pintype "passive"))
    )
    (net (code "70") (name "5V") (class "Default")
      (node (ref "C1") (pin "2") (pinfunction "2_2") (pintype "passive"))
      (node (ref "F1") (pin "2") (pinfunction "2_2") (pintype "passive"))
      (node (ref "IC2") (pin "10") (pinfunction "VCC_10") (pintype "power_in"))
      (node (ref "IC3") (pin "4") (pinfunction "VCC_4") (pintype "bidirectional"))
      (node (ref "J1") (pin "5") (pinfunction "5_5") (pintype "passive"))
      (node (ref "LED1") (pin "A") (pinfunction "A_A") (pintype "passive"))
      (node (ref "LED2") (pin "A") (pinfunction "A_A") (pintype "passive"))
      (node (ref "LED7") (pin "A") (pinfunction "A_A") (pintype "passive"))
      (node (ref "R13") (pin "1") (pinfunction "1_1") (pintype "passive"))
      (node (ref "R14") (pin "1") (pinfunction "1_1") (pintype "passive"))
    )
    (net (code "71") (name "GND") (class "Default")
      (node (ref "C1") (pin "1") (pinfunction "1_1") (pintype "passive"))
      (node (ref "C10") (pin "1") (pinfunction "1_1") (pintype "passive"))
      (node (ref "C11") (pin "2") (pinfunction "2_2") (pintype "passive"))
      (node (ref "C18") (pin "1") (pinfunction "1_1") (pintype "passive"))
      (node (ref "C19") (pin "1") (pinfunction "1_1") (pintype "passive"))
      (node (ref "C20") (pin "1") (pinfunction "1_1") (pintype "passive"))
      (node (ref "C21") (pin "1") (pinfunction "1_1") (pintype "passive"))
      (node (ref "C4") (pin "2") (pinfunction "2_2") (pintype "passive"))
      (node (ref "C5") (pin "-") (pinfunction "-_-") (pintype "passive"))
      (node (ref "C6") (pin "-") (pinfunction "-_-") (pintype "passive"))
      (node (ref "C7") (pin "1") (pinfunction "1_1") (pintype "passive"))
      (node (ref "C9") (pin "2") (pinfunction "2_2") (pintype "passive"))
      (node (ref "IC1") (pin "18") (pinfunction "GND_18") (pintype "bidirectional"))
      (node (ref "IC1") (pin "28") (pinfunction "GND_28") (pintype "bidirectional"))
      (node (ref "IC1") (pin "39") (pinfunction "GND_39") (pintype "bidirectional"))
      (node (ref "IC1") (pin "6") (pinfunction "GND_6") (pintype "bidirectional"))
      (node (ref "IC1") (pin "TGND") (pinfunction "TGND_TGND") (pintype "bidirectional"))
      (node (ref "IC2") (pin "13") (pinfunction "GND_13") (pintype "bidirectional"))
      (node (ref "IC2") (pin "3") (pinfunction "GND_3") (pintype "bidirectional"))
      (node (ref "IC2") (pin "TGND") (pinfunction "GND_TGND") (pintype "bidirectional"))
      (node (ref "IC3") (pin "2") (pinfunction "GND_2") (pintype "bidirectional"))
      (node (ref "IC4") (pin "2") (pinfunction "GND_2") (pintype "power_in"))
      (node (ref "IC5") (pin "17") (pinfunction "GND_17") (pintype "power_in"))
      (node (ref "IC5") (pin "18") (pinfunction "GND_18") (pintype "power_in"))
      (node (ref "IC5") (pin "29") (pinfunction "GND_29") (pintype "power_in"))
      (node (ref "IC5") (pin "39") (pinfunction "GND_39") (pintype "power_in"))
      (node (ref "IC5") (pin "45") (pinfunction "GND_45") (pintype "power_in"))
      (node (ref "IC5") (pin "46") (pinfunction "GND_46") (pintype "power_in"))
      (node (ref "IC5") (pin "53") (pinfunction "GND_53") (pintype "power_in"))
      (node (ref "IC5") (pin "54") (pinfunction "GND_54") (pintype "power_in"))
      (node (ref "IC5") (pin "58") (pinfunction "GND_58") (pintype "power_in"))
      (node (ref "IC5") (pin "59") (pinfunction "GND_59") (pintype "power_in"))
      (node (ref "IC5") (pin "61") (pinfunction "GND_61") (pintype "power_in"))
      (node (ref "IC5") (pin "62") (pinfunction "GND_62") (pintype "power_in"))
      (node (ref "IC5") (pin "63") (pinfunction "GND_63") (pintype "power_in"))
      (node (ref "IC5") (pin "64") (pinfunction "GND_64") (pintype "power_in"))
      (node (ref "IC5") (pin "65") (pinfunction "GND_65") (pintype "power_in"))
      (node (ref "J1") (pin "6") (pinfunction "6_6") (pintype "passive"))
      (node (ref "J1") (pin "7") (pinfunction "7_7") (pintype "passive"))
      (node (ref "J3") (pin "7") (pinfunction "7_7") (pintype "passive"))
      (node (ref "J6") (pin "6") (pinfunction "GND_6") (pintype "bidirectional"))
      (node (ref "JP1") (pin "2") (pinfunction "2_2") (pintype "passive"))
      (node (ref "JP11") (pin "1") (pinfunction "1_1") (pintype "passive"))
      (node (ref "JP14") (pin "2") (pinfunction "2_2") (pintype "passive"))
      (node (ref "L1") (pin "2") (pinfunction "2_2") (pintype "passive"))
      (node (ref "P1") (pin "GND") (pinfunction "GND_GND") (pintype "bidirectional"))
      (node (ref "P2") (pin "6") (pinfunction "6_6") (pintype "passive"))
      (node (ref "Q1") (pin "2") (pinfunction "S_2") (pintype "passive"))
      (node (ref "Q2") (pin "2") (pinfunction "S_2") (pintype "passive"))
      (node (ref "Q4") (pin "2") (pinfunction "S_2") (pintype "passive"))
      (node (ref "R10") (pin "1") (pinfunction "1_1") (pintype "passive"))
      (node (ref "R15") (pin "2") (pinfunction "2_2") (pintype "passive"))
      (node (ref "R16") (pin "2") (pinfunction "2_2") (pintype "passive"))
      (node (ref "R17") (pin "2") (pinfunction "2_2") (pintype "passive"))
      (node (ref "R19") (pin "1") (pinfunction "1_1") (pintype "passive"))
      (node (ref "R25") (pin "1") (pinfunction "1_1") (pintype "passive"))
      (node (ref "S1") (pin "1") (pinfunction "P_1") (pintype "passive"))
      (node (ref "S2") (pin "NEG") (pinfunction "NEG_NEG") (pintype "power_in"))
      (node (ref "S3") (pin "2") (pinfunction "2_2") (pintype "passive"))
      (node (ref "U$9") (pin "-") (pinfunction "-_-") (pintype "bidirectional"))
      (node (ref "Y1") (pin "2") (pinfunction "2_2") (pintype "passive"))
      (node (ref "Z1") (pin "3") (pinfunction "P$3_3") (pintype "bidirectional"))
      (node (ref "Z2") (pin "3") (pinfunction "P$3_3") (pintype "bidirectional"))
    )
    (net (code "72") (name "Net-(C8-Pad1)") (class "Default")
      (node (ref "C8") (pin "1") (pinfunction "1_1") (pintype "passive"))
      (node (ref "SJ1") (pin "2") (pinfunction "2_2") (pintype "passive"))
    )
    (net (code "73") (name "Net-(C12-Pad1)") (class "Default")
      (node (ref "C12") (pin "1") (pinfunction "1_1") (pintype "passive"))
      (node (ref "P1") (pin "D+") (pinfunction "D+_D+") (pintype "bidirectional"))
      (node (ref "R12") (pin "2") (pinfunction "2_2") (pintype "passive"))
    )
    (net (code "74") (name "Net-(C12-Pad2)") (class "Default")
      (node (ref "C12") (pin "2") (pinfunction "2_2") (pintype "passive"))
      (node (ref "C13") (pin "2") (pinfunction "2_2") (pintype "passive"))
      (node (ref "L1") (pin "1") (pinfunction "1_1") (pintype "passive"))
      (node (ref "P1") (pin "FIX1") (pinfunction "FIX1_FIX1") (pintype "bidirectional"))
      (node (ref "P1") (pin "FIX2") (pinfunction "FIX2_FIX2") (pintype "bidirectional"))
      (node (ref "P1") (pin "PIN1") (pinfunction "PIN1_PIN1") (pintype "bidirectional"))
      (node (ref "P1") (pin "PIN2") (pinfunction "PIN2_PIN2") (pintype "bidirectional"))
      (node (ref "P1") (pin "TAB1") (pinfunction "TAB1_TAB1") (pintype "bidirectional"))
      (node (ref "P1") (pin "TAB2") (pinfunction "TAB2_TAB2") (pintype "bidirectional"))
    )
    (net (code "75") (name "Net-(C13-Pad1)") (class "Default")
      (node (ref "C13") (pin "1") (pinfunction "1_1") (pintype "passive"))
      (node (ref "P1") (pin "D-") (pinfunction "D-_D-") (pintype "bidirectional"))
      (node (ref "R11") (pin "2") (pinfunction "2_2") (pintype "passive"))
    )
    (net (code "76") (name "Net-(F1-Pad1)") (class "Default")
      (node (ref "F1") (pin "1") (pinfunction "1_1") (pintype "passive"))
      (node (ref "P1") (pin "VBUS") (pinfunction "VBUS_VBUS") (pintype "bidirectional"))
    )
    (net (code "77") (name "Net-(IC1-XTAL1)") (class "Default")
      (node (ref "IC1") (pin "8") (pinfunction "XTAL1_8") (pintype "bidirectional"))
      (node (ref "Y1") (pin "3") (pinfunction "3_3") (pintype "passive"))
    )
    (net (code "78") (name "Net-(IC1-XTAL2)") (class "Default")
      (node (ref "IC1") (pin "7") (pinfunction "XTAL2_7") (pintype "bidirectional"))
      (node (ref "Y1") (pin "1") (pinfunction "1_1") (pintype "passive"))
    )
    (net (code "79") (name "Net-(IC2-3V3OUT)") (class "Default")
      (node (ref "C11") (pin "1") (pinfunction "1_1") (pintype "passive"))
      (node (ref "IC2") (pin "1") (pinfunction "VCCIO_1") (pintype "power_in"))
      (node (ref "IC2") (pin "8") (pinfunction "3V3OUT_8") (pintype "power_in"))
      (node (ref "IC2") (pin "9") (pinfunction "~{RESET}_9") (pintype "input"))
    )
    (net (code "80") (name "Net-(IC3-PROG)") (class "Default")
      (node (ref "IC3") (pin "5") (pinfunction "PROG_5") (pintype "bidirectional"))
      (node (ref "R15") (pin "1") (pinfunction "1_1") (pintype "passive"))
      (node (ref "SJ4") (pin "2") (pinfunction "2_2") (pintype "passive"))
      (node (ref "SJ5") (pin "2") (pinfunction "2_2") (pintype "passive"))
    )
    (net (code "81") (name "Net-(IC3-~{CHRG})") (class "Default")
      (node (ref "IC3") (pin "1") (pinfunction "~{CHRG}_1") (pintype "bidirectional"))
      (node (ref "LED5") (pin "C") (pinfunction "C_C") (pintype "passive"))
      (node (ref "Q1") (pin "1") (pinfunction "G_1") (pintype "passive"))
      (node (ref "R14") (pin "2") (pinfunction "2_2") (pintype "passive"))
    )
    (net (code "82") (name "Net-(IC5-PWRKEY)") (class "Default")
      (node (ref "IC5") (pin "1") (pinfunction "PWRKEY_1") (pintype "input"))
      (node (ref "R6") (pin "2") (pinfunction "2_2") (pintype "passive"))
    )
    (net (code "83") (name "Net-(IC5-VRTC)") (class "Default")
      (node (ref "IC5") (pin "26") (pinfunction "VRTC_26") (pintype "bidirectional"))
      (node (ref "U$9") (pin "+") (pinfunction "+_+") (pintype "bidirectional"))
    )
    (net (code "84") (name "Net-(J6-CLK)") (class "Default")
      (node (ref "J6") (pin "3") (pinfunction "CLK_3") (pintype "bidirectional"))
      (node (ref "R22") (pin "2") (pinfunction "2_2") (pintype "passive"))
      (node (ref "Z1") (pin "1") (pinfunction "P$1_1") (pintype "bidirectional"))
    )
    (net (code "85") (name "Net-(J6-I{slash}O)") (class "Default")
      (node (ref "J6") (pin "4") (pinfunction "I/O_4") (pintype "bidirectional"))
      (node (ref "R24") (pin "2") (pinfunction "2_2") (pintype "passive"))
      (node (ref "Z1") (pin "2") (pinfunction "P$2_2") (pintype "bidirectional"))
    )
    (net (code "86") (name "Net-(J6-RST)") (class "Default")
      (node (ref "J6") (pin "2") (pinfunction "RST_2") (pintype "bidirectional"))
      (node (ref "R23") (pin "2") (pinfunction "2_2") (pintype "passive"))
      (node (ref "Z2") (pin "1") (pinfunction "P$1_1") (pintype "bidirectional"))
    )
    (net (code "87") (name "Net-(JP12-Pad1)") (class "Default")
      (node (ref "JP12") (pin "1") (pinfunction "1_1") (pintype "passive"))
      (node (ref "SJ2") (pin "1") (pinfunction "1_1") (pintype "passive"))
    )
    (net (code "88") (name "Net-(LED1-PadC)") (class "Default")
      (node (ref "LED1") (pin "C") (pinfunction "C_C") (pintype "passive"))
      (node (ref "R2") (pin "2") (pinfunction "2_2") (pintype "passive"))
    )
    (net (code "89") (name "Net-(LED2-PadC)") (class "Default")
      (node (ref "LED2") (pin "C") (pinfunction "C_C") (pintype "passive"))
      (node (ref "R3") (pin "2") (pinfunction "2_2") (pintype "passive"))
    )
    (net (code "90") (name "Net-(LED3-PadC)") (class "Default")
      (node (ref "LED3") (pin "C") (pinfunction "C_C") (pintype "passive"))
      (node (ref "R7") (pin "2") (pinfunction "2_2") (pintype "passive"))
    )
    (net (code "91") (name "Net-(LED4-PadC)") (class "Default")
      (node (ref "LED4") (pin "C") (pinfunction "C_C") (pintype "passive"))
      (node (ref "R10") (pin "2") (pinfunction "2_2") (pintype "passive"))
    )
    (net (code "92") (name "Net-(LED5-PadA)") (class "Default")
      (node (ref "LED5") (pin "A") (pinfunction "A_A") (pintype "passive"))
      (node (ref "LED6") (pin "A") (pinfunction "A_A") (pintype "passive"))
      (node (ref "R13") (pin "2") (pinfunction "2_2") (pintype "passive"))
    )
    (net (code "93") (name "Net-(LED7-PadC)") (class "Default")
      (node (ref "LED7") (pin "C") (pinfunction "C_C") (pintype "passive"))
      (node (ref "R19") (pin "2") (pinfunction "2_2") (pintype "passive"))
    )
    (net (code "94") (name "Net-(Q1-D)") (class "Default")
      (node (ref "LED6") (pin "C") (pinfunction "C_C") (pintype "passive"))
      (node (ref "Q1") (pin "3") (pinfunction "D_3") (pintype "passive"))
    )
    (net (code "95") (name "Net-(Q2-D)") (class "Default")
      (node (ref "Q2") (pin "3") (pinfunction "D_3") (pintype "passive"))
      (node (ref "R7") (pin "1") (pinfunction "1_1") (pintype "passive"))
    )
    (net (code "96") (name "Net-(Q4-D)") (class "Default")
      (node (ref "Q4") (pin "3") (pinfunction "D_3") (pintype "passive"))
      (node (ref "R6") (pin "1") (pinfunction "1_1") (pintype "passive"))
    )
    (net (code "97") (name "Net-(Q4-G)") (class "Default")
      (node (ref "Q4") (pin "1") (pinfunction "G_1") (pintype "passive"))
      (node (ref "R25") (pin "2") (pinfunction "2_2") (pintype "passive"))
      (node (ref "R26") (pin "1") (pinfunction "1_1") (pintype "passive"))
    )
    (net (code "98") (name "Net-(R16-Pad1)") (class "Default")
      (node (ref "R16") (pin "1") (pinfunction "1_1") (pintype "passive"))
      (node (ref "SJ4") (pin "1") (pinfunction "1_1") (pintype "passive"))
    )
    (net (code "99") (name "Net-(R17-Pad1)") (class "Default")
      (node (ref "R17") (pin "1") (pinfunction "1_1") (pintype "passive"))
      (node (ref "SJ5") (pin "1") (pinfunction "1_1") (pintype "passive"))
    )
    (net (code "100") (name "VCC") (class "Default")
      (node (ref "C10") (pin "2") (pinfunction "2_2") (pintype "passive"))
      (node (ref "C21") (pin "2") (pinfunction "2_2") (pintype "passive"))
      (node (ref "C5") (pin "+") (pinfunction "+_+") (pintype "passive"))
      (node (ref "C6") (pin "+") (pinfunction "+_+") (pintype "passive"))
      (node (ref "IC3") (pin "3") (pinfunction "BAT_3") (pintype "bidirectional"))
      (node (ref "IC4") (pin "1") (pinfunction "IN_1") (pintype "input"))
      (node (ref "IC4") (pin "3") (pinfunction "~{EN}_3") (pintype "input"))
      (node (ref "IC5") (pin "55") (pinfunction "VBAT_55") (pintype "power_in"))
      (node (ref "IC5") (pin "56") (pinfunction "VBAT_56") (pintype "power_in"))
      (node (ref "IC5") (pin "57") (pinfunction "VBAT_57") (pintype "power_in"))
      (node (ref "J1") (pin "8") (pinfunction "8_8") (pintype "passive"))
      (node (ref "JP1") (pin "1") (pinfunction "1_1") (pintype "passive"))
      (node (ref "S2") (pin "POS") (pinfunction "POS_POS") (pintype "power_in"))
      (node (ref "S3") (pin "1") (pinfunction "1_1") (pintype "passive"))
    )
    (net (code "101") (name "unconnected-(IC1-PB0(PCINT8{slash}XCK0{slash}T0)-Pad40)") (class "Default")
      (node (ref "IC1") (pin "40") (pinfunction "PB0(PCINT8/XCK0/T0)_40") (pintype "bidirectional"))
    )
    (net (code "102") (name "unconnected-(IC1-PB1(PCINT9{slash}CLKO{slash}T1)-Pad41)") (class "Default")
      (node (ref "IC1") (pin "41") (pinfunction "PB1(PCINT9/CLKO/T1)_41") (pintype "bidirectional"))
    )
    (net (code "103") (name "unconnected-(IC2-CBUS0-Pad12)") (class "Default")
      (node (ref "IC2") (pin "12") (pinfunction "CBUS0_12") (pintype "bidirectional"))
    )
    (net (code "104") (name "unconnected-(IC2-CBUS3-Pad14)") (class "Default")
      (node (ref "IC2") (pin "14") (pinfunction "CBUS3_14") (pintype "bidirectional"))
    )
    (net (code "105") (name "unconnected-(IC2-~{CTS}-Pad4)") (class "Default")
      (node (ref "IC2") (pin "4") (pinfunction "~{CTS}_4") (pintype "bidirectional"))
    )
    (net (code "106") (name "unconnected-(IC4-NC{slash}FB-Pad4)") (class "Default")
      (node (ref "IC4") (pin "4") (pinfunction "NC/FB_4") (pintype "passive"))
    )
    (net (code "107") (name "unconnected-(IC5-ADC-Pad25)") (class "Default")
      (node (ref "IC5") (pin "25") (pinfunction "ADC_25") (pintype "input"))
    )
    (net (code "108") (name "unconnected-(IC5-DTR-Pad3)") (class "Default")
      (node (ref "IC5") (pin "3") (pinfunction "DTR_3") (pintype "input"))
    )
    (net (code "109") (name "unconnected-(IC5-GPIO1{slash}KBR4-Pad40)") (class "Default")
      (node (ref "IC5") (pin "40") (pinfunction "GPIO1/KBR4_40") (pintype "output"))
    )
    (net (code "110") (name "unconnected-(IC5-GPIO2{slash}KBR3-Pad41)") (class "Default")
      (node (ref "IC5") (pin "41") (pinfunction "GPIO2/KBR3_41") (pintype "output"))
    )
    (net (code "111") (name "unconnected-(IC5-GPIO3{slash}KBR2-Pad42)") (class "Default")
      (node (ref "IC5") (pin "42") (pinfunction "GPIO3/KBR2_42") (pintype "output"))
    )
    (net (code "112") (name "unconnected-(IC5-GPIO4{slash}KBR1-Pad43)") (class "Default")
      (node (ref "IC5") (pin "43") (pinfunction "GPIO4/KBR1_43") (pintype "output"))
    )
    (net (code "113") (name "unconnected-(IC5-GPIO5{slash}KBR0-Pad44)") (class "Default")
      (node (ref "IC5") (pin "44") (pinfunction "GPIO5/KBR0_44") (pintype "output"))
    )
    (net (code "114") (name "unconnected-(IC5-GPIO6{slash}KBC4-Pad47)") (class "Default")
      (node (ref "IC5") (pin "47") (pinfunction "GPIO6/KBC4_47") (pintype "input"))
    )
    (net (code "115") (name "unconnected-(IC5-GPIO7{slash}KBC3-Pad48)") (class "Default")
      (node (ref "IC5") (pin "48") (pinfunction "GPIO7/KBC3_48") (pintype "bidirectional"))
    )
    (net (code "116") (name "unconnected-(IC5-GPIO8{slash}KBC2-Pad49)") (class "Default")
      (node (ref "IC5") (pin "49") (pinfunction "GPIO8/KBC2_49") (pintype "input"))
    )
    (net (code "117") (name "unconnected-(IC5-GPIO9{slash}KBC1-Pad50)") (class "Default")
      (node (ref "IC5") (pin "50") (pinfunction "GPIO9/KBC1_50") (pintype "input"))
    )
    (net (code "118") (name "unconnected-(IC5-GPIO10{slash}KBC0-Pad51)") (class "Default")
      (node (ref "IC5") (pin "51") (pinfunction "GPIO10/KBC0_51") (pintype "bidirectional"))
    )
    (net (code "119") (name "unconnected-(IC5-GPIO11-Pad67)") (class "Default")
      (node (ref "IC5") (pin "67") (pinfunction "GPIO11_67") (pintype "bidirectional"))
    )
    (net (code "120") (name "unconnected-(IC5-GPIO12-Pad68)") (class "Default")
      (node (ref "IC5") (pin "68") (pinfunction "GPIO12_68") (pintype "bidirectional"))
    )
    (net (code "121") (name "unconnected-(IC5-LINEIN_L-Pad24)") (class "Default")
      (node (ref "IC5") (pin "24") (pinfunction "LINEIN_L_24") (pintype "input"))
    )
    (net (code "122") (name "unconnected-(IC5-LINEIN_R-Pad23)") (class "Default")
      (node (ref "IC5") (pin "23") (pinfunction "LINEIN_R_23") (pintype "input"))
    )
    (net (code "123") (name "unconnected-(IC5-PWM1-Pad35)") (class "Default")
      (node (ref "IC5") (pin "35") (pinfunction "PWM1_35") (pintype "output"))
    )
    (net (code "124") (name "unconnected-(IC5-PWM2-Pad36)") (class "Default")
      (node (ref "IC5") (pin "36") (pinfunction "PWM2_36") (pintype "output"))
    )
    (net (code "125") (name "unconnected-(IC5-PWRKEY_OUT-Pad2)") (class "Default")
      (node (ref "IC5") (pin "2") (pinfunction "PWRKEY_OUT_2") (pintype "output"))
    )
    (net (code "126") (name "unconnected-(IC5-SCL-Pad38)") (class "Default")
      (node (ref "IC5") (pin "38") (pinfunction "SCL_38") (pintype "output"))
    )
    (net (code "127") (name "unconnected-(IC5-SDA-Pad37)") (class "Default")
      (node (ref "IC5") (pin "37") (pinfunction "SDA_37") (pintype "bidirectional"))
    )
    (net (code "128") (name "unconnected-(IC5-SIM_PRESENCE-Pad34)") (class "Default")
      (node (ref "IC5") (pin "34") (pinfunction "SIM_PRESENCE_34") (pintype "input"))
    )
    (net (code "129") (name "unconnected-(IC5-VDD_EXT-Pad15)") (class "Default")
      (node (ref "IC5") (pin "15") (pinfunction "VDD_EXT_15") (pintype "output"))
    )
    (net (code "130") (name "unconnected-(J1-Pad1)") (class "Default")
      (node (ref "J1") (pin "1") (pinfunction "1_1") (pintype "passive"))
    )
    (net (code "131") (name "unconnected-(J6-VPP-Pad5)") (class "Default")
      (node (ref "J6") (pin "5") (pinfunction "VPP_5") (pintype "bidirectional"))
    )
    (net (code "132") (name "unconnected-(JP1-Pad4)") (class "Default")
      (node (ref "JP1") (pin "4") (pinfunction "4_4") (pintype "passive"))
    )
    (net (code "133") (name "unconnected-(P1-PadID)") (class "Default")
      (node (ref "P1") (pin "ID") (pinfunction "ID_ID") (pintype "bidirectional"))
    )
  )
)
